# RS485.net
KiCad netlist of a schematic drawn in Altium Designer
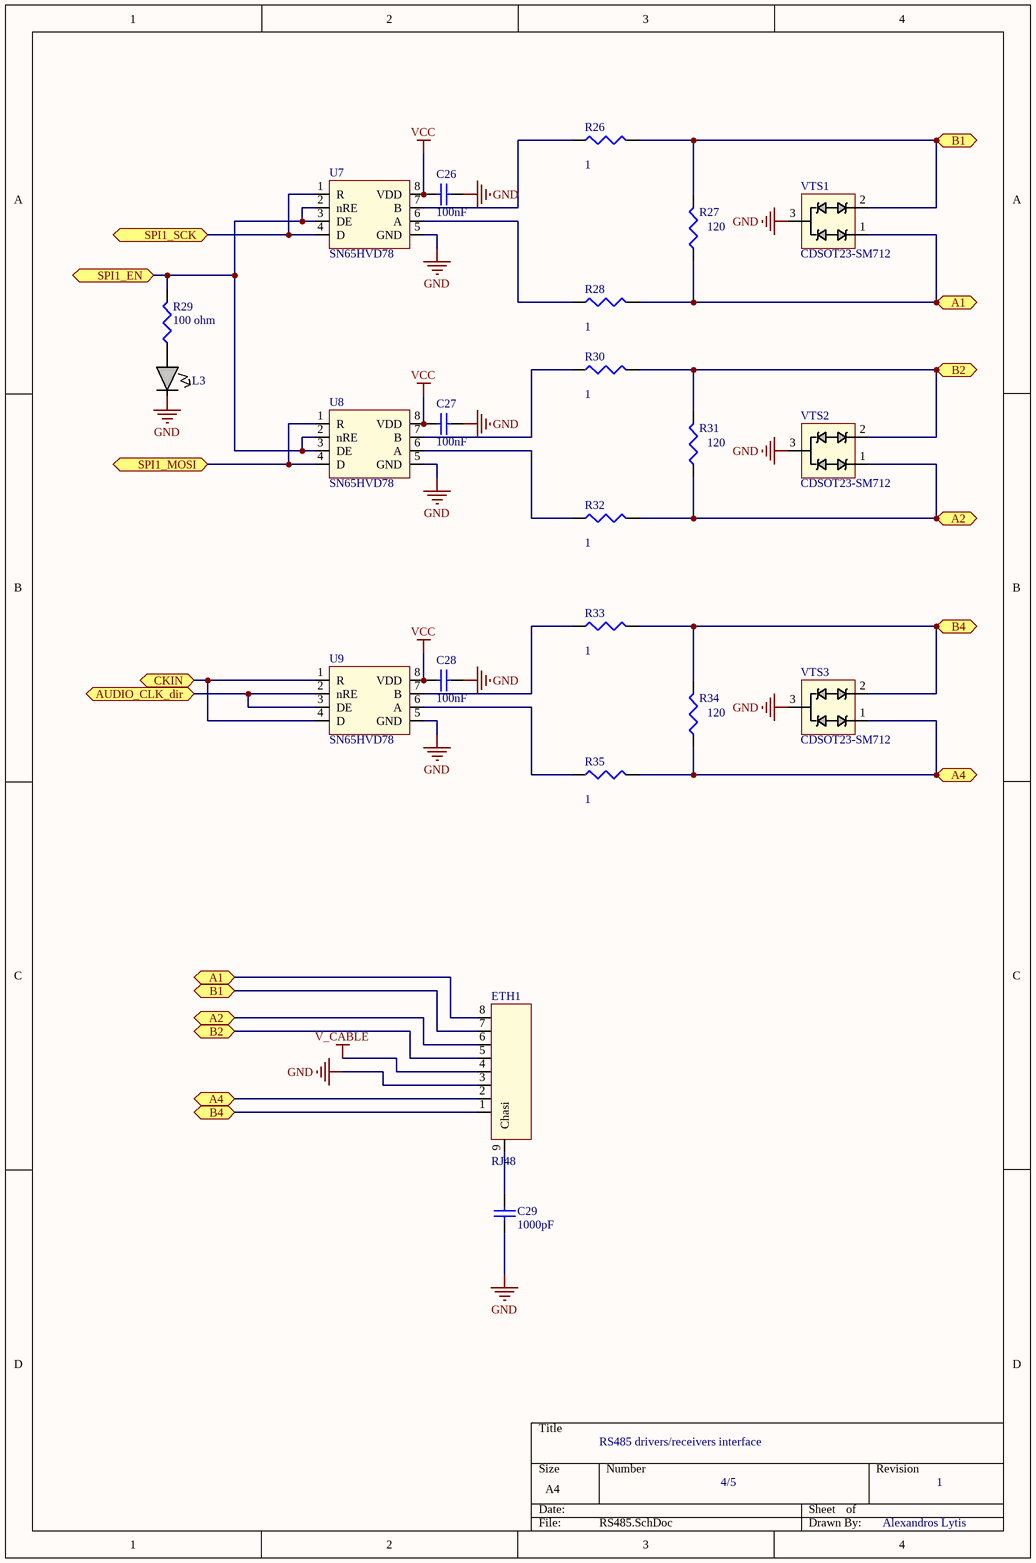
[diagram p0: RS485.SchDoc]

(export (version "E")
  (design (tool "Eeschema 10.0.6"))
  (components
    (comp (ref "C26")
      (value "100nF")
      (footprint "CAP0603")
      (description "Capacitor (Semiconductor SIM Model)")
      (fields (field (name "Comment") "Cap Semi") (field (name "PUBLISHER") "Altium Limited"))
      (libsource (lib "Miscellaneous Devices") (part "Cap Semi"))
    )
    (comp (ref "C27")
      (value "100nF")
      (footprint "CAP0603")
      (description "Capacitor (Semiconductor SIM Model)")
      (fields (field (name "Comment") "Cap Semi") (field (name "PUBLISHER") "Altium Limited"))
      (libsource (lib "Miscellaneous Devices") (part "Cap Semi"))
    )
    (comp (ref "C28")
      (value "100nF")
      (footprint "CAP0603")
      (description "Capacitor (Semiconductor SIM Model)")
      (fields (field (name "Comment") "Cap Semi") (field (name "PUBLISHER") "Altium Limited"))
      (libsource (lib "Miscellaneous Devices") (part "Cap Semi"))
    )
    (comp (ref "C29")
      (value "1000pF")
      (footprint "CAP0603")
      (description "Capacitor (Semiconductor SIM Model)")
      (fields (field (name "Comment") "Cap Semi") (field (name "PUBLISHER") "Altium Limited"))
      (libsource (lib "Miscellaneous Devices") (part "Cap Semi"))
    )
    (comp (ref "ETH1")
      (value "RJ48")
      (footprint "TE modular Jack RJ45")
      (libsource (lib "Custom_Libraries") (part "Ethernet Jack"))
    )
    (comp (ref "L3")
      (value "LED_1.6x0.8mm")
      (footprint "J1-0603")
      (libsource (lib "Custom_Libraries") (part "LED_1.6x0.8mm"))
    )
    (comp (ref "R26")
      (value "1")
      (footprint "RES0603")
      (description "Resistor")
      (fields (field (name "Comment") "pulse-proof") (field (name "PUBLISHER") "Altium Limited"))
      (libsource (lib "Miscellaneous Devices") (part "Res3"))
    )
    (comp (ref "R27")
      (value "120")
      (footprint "RES0603")
      (description "Resistor")
      (fields (field (name "Comment") "pulse-proof") (field (name "PUBLISHER") "Altium Limited"))
      (libsource (lib "Miscellaneous Devices") (part "Res3"))
    )
    (comp (ref "R28")
      (value "1")
      (footprint "RES0603")
      (description "Resistor")
      (fields (field (name "Comment") "pulse-proof") (field (name "PUBLISHER") "Altium Limited"))
      (libsource (lib "Miscellaneous Devices") (part "Res3"))
    )
    (comp (ref "R29")
      (value "100 ohm")
      (footprint "RES0603")
      (description "Resistor")
      (fields (field (name "Comment") "Res3") (field (name "PUBLISHER") "Altium Limited"))
      (libsource (lib "Miscellaneous Devices") (part "Res3"))
    )
    (comp (ref "R30")
      (value "1")
      (footprint "RES0603")
      (description "Resistor")
      (fields (field (name "Comment") "pulse-proof") (field (name "PUBLISHER") "Altium Limited"))
      (libsource (lib "Miscellaneous Devices") (part "Res3"))
    )
    (comp (ref "R31")
      (value "120")
      (footprint "RES0603")
      (description "Resistor")
      (fields (field (name "Comment") "pulse-proof") (field (name "PUBLISHER") "Altium Limited"))
      (libsource (lib "Miscellaneous Devices") (part "Res3"))
    )
    (comp (ref "R32")
      (value "1")
      (footprint "RES0603")
      (description "Resistor")
      (fields (field (name "Comment") "pulse-proof") (field (name "PUBLISHER") "Altium Limited"))
      (libsource (lib "Miscellaneous Devices") (part "Res3"))
    )
    (comp (ref "R33")
      (value "1")
      (footprint "RES0603")
      (description "Resistor")
      (fields (field (name "Comment") "pulse-proof") (field (name "PUBLISHER") "Altium Limited"))
      (libsource (lib "Miscellaneous Devices") (part "Res3"))
    )
    (comp (ref "R34")
      (value "120")
      (footprint "RES0603")
      (description "Resistor")
      (fields (field (name "Comment") "pulse-proof") (field (name "PUBLISHER") "Altium Limited"))
      (libsource (lib "Miscellaneous Devices") (part "Res3"))
    )
    (comp (ref "R35")
      (value "1")
      (footprint "RES0603")
      (description "Resistor")
      (fields (field (name "Comment") "pulse-proof") (field (name "PUBLISHER") "Altium Limited"))
      (libsource (lib "Miscellaneous Devices") (part "Res3"))
    )
    (comp (ref "U7")
      (value "SN65HVD78")
      (footprint "SOP127P600-8N")
      (libsource (lib "Custom_Libraries") (part "sn65hvd7x"))
    )
    (comp (ref "U8")
      (value "SN65HVD78")
      (footprint "SOP127P600-8N")
      (libsource (lib "Custom_Libraries") (part "sn65hvd7x"))
    )
    (comp (ref "U9")
      (value "SN65HVD78")
      (footprint "SOP127P600-8N")
      (libsource (lib "Custom_Libraries") (part "sn65hvd7x"))
    )
    (comp (ref "VTS1")
      (value "CDSOT23-SM712")
      (footprint "SOT190P230X117-3N")
      (libsource (lib "Custom_Libraries") (part "CDSOT23-SM712"))
    )
    (comp (ref "VTS2")
      (value "CDSOT23-SM712")
      (footprint "SOT190P230X117-3N")
      (libsource (lib "Custom_Libraries") (part "CDSOT23-SM712"))
    )
    (comp (ref "VTS3")
      (value "CDSOT23-SM712")
      (footprint "SOT190P230X117-3N")
      (libsource (lib "Custom_Libraries") (part "CDSOT23-SM712"))
    )
  )
  (nets
    (net (code "1") (name "/A1") (class "Default")
      (node (ref "ETH1") (pin "8") (pintype "passive"))
      (node (ref "R27") (pin "1") (pinfunction "1_1") (pintype "passive"))
      (node (ref "R28") (pin "2") (pinfunction "2_2") (pintype "passive"))
      (node (ref "VTS1") (pin "1") (pintype "passive"))
    )
    (net (code "2") (name "/A2") (class "Default")
      (node (ref "ETH1") (pin "6") (pintype "passive"))
      (node (ref "R31") (pin "1") (pinfunction "1_1") (pintype "passive"))
      (node (ref "R32") (pin "2") (pinfunction "2_2") (pintype "passive"))
      (node (ref "VTS2") (pin "1") (pintype "passive"))
    )
    (net (code "3") (name "/A4") (class "Default")
      (node (ref "ETH1") (pin "2") (pintype "passive"))
      (node (ref "R34") (pin "1") (pinfunction "1_1") (pintype "passive"))
      (node (ref "R35") (pin "2") (pinfunction "2_2") (pintype "passive"))
      (node (ref "VTS3") (pin "1") (pintype "passive"))
    )
    (net (code "4") (name "/AUDIO_CLK_dir") (class "Default")
      (node (ref "U9") (pin "2") (pinfunction "nRE_2") (pintype "passive"))
      (node (ref "U9") (pin "3") (pinfunction "DE_3") (pintype "passive"))
    )
    (net (code "5") (name "/B1") (class "Default")
      (node (ref "ETH1") (pin "7") (pintype "passive"))
      (node (ref "R26") (pin "2") (pinfunction "2_2") (pintype "passive"))
      (node (ref "R27") (pin "2") (pinfunction "2_2") (pintype "passive"))
      (node (ref "VTS1") (pin "2") (pintype "passive"))
    )
    (net (code "6") (name "/B2") (class "Default")
      (node (ref "ETH1") (pin "5") (pintype "passive"))
      (node (ref "R30") (pin "2") (pinfunction "2_2") (pintype "passive"))
      (node (ref "R31") (pin "2") (pinfunction "2_2") (pintype "passive"))
      (node (ref "VTS2") (pin "2") (pintype "passive"))
    )
    (net (code "7") (name "/B4") (class "Default")
      (node (ref "ETH1") (pin "1") (pintype "passive"))
      (node (ref "R33") (pin "2") (pinfunction "2_2") (pintype "passive"))
      (node (ref "R34") (pin "2") (pinfunction "2_2") (pintype "passive"))
      (node (ref "VTS3") (pin "2") (pintype "passive"))
    )
    (net (code "8") (name "/CKIN") (class "Default")
      (node (ref "U9") (pin "1") (pinfunction "R_1") (pintype "passive"))
      (node (ref "U9") (pin "4") (pinfunction "D_4") (pintype "passive"))
    )
    (net (code "9") (name "/SPI1_EN") (class "Default")
      (node (ref "R29") (pin "2") (pinfunction "2_2") (pintype "passive"))
      (node (ref "U7") (pin "2") (pinfunction "nRE_2") (pintype "passive"))
      (node (ref "U7") (pin "3") (pinfunction "DE_3") (pintype "passive"))
      (node (ref "U8") (pin "2") (pinfunction "nRE_2") (pintype "passive"))
      (node (ref "U8") (pin "3") (pinfunction "DE_3") (pintype "passive"))
    )
    (net (code "10") (name "/SPI1_MOSI") (class "Default")
      (node (ref "U8") (pin "1") (pinfunction "R_1") (pintype "passive"))
      (node (ref "U8") (pin "4") (pinfunction "D_4") (pintype "passive"))
    )
    (net (code "11") (name "/SPI1_SCK") (class "Default")
      (node (ref "U7") (pin "1") (pinfunction "R_1") (pintype "passive"))
      (node (ref "U7") (pin "4") (pinfunction "D_4") (pintype "passive"))
    )
    (net (code "12") (name "GND") (class "Default")
      (node (ref "C26") (pin "2") (pinfunction "2_2") (pintype "passive"))
      (node (ref "C27") (pin "2") (pinfunction "2_2") (pintype "passive"))
      (node (ref "C28") (pin "2") (pinfunction "2_2") (pintype "passive"))
      (node (ref "C29") (pin "1") (pinfunction "1_1") (pintype "passive"))
      (node (ref "ETH1") (pin "3") (pintype "passive"))
      (node (ref "L3") (pin "2") (pintype "passive"))
      (node (ref "U7") (pin "5") (pinfunction "GND_5") (pintype "passive"))
      (node (ref "U8") (pin "5") (pinfunction "GND_5") (pintype "passive"))
      (node (ref "U9") (pin "5") (pinfunction "GND_5") (pintype "passive"))
      (node (ref "VTS1") (pin "3") (pintype "passive"))
      (node (ref "VTS2") (pin "3") (pintype "passive"))
      (node (ref "VTS3") (pin "3") (pintype "passive"))
    )
    (net (code "13") (name "Net-(ETH1-Chasi)") (class "Default")
      (node (ref "C29") (pin "2") (pinfunction "2_2") (pintype "passive"))
      (node (ref "ETH1") (pin "9") (pinfunction "Chasi_9") (pintype "passive"))
    )
    (net (code "14") (name "Net-(L3-Pad1)") (class "Default")
      (node (ref "L3") (pin "1") (pintype "passive"))
      (node (ref "R29") (pin "1") (pinfunction "1_1") (pintype "passive"))
    )
    (net (code "15") (name "Net-(U7-A)") (class "Default")
      (node (ref "R28") (pin "1") (pinfunction "1_1") (pintype "passive"))
      (node (ref "U7") (pin "6") (pinfunction "A_6") (pintype "passive"))
    )
    (net (code "16") (name "Net-(U7-B)") (class "Default")
      (node (ref "R26") (pin "1") (pinfunction "1_1") (pintype "passive"))
      (node (ref "U7") (pin "7") (pinfunction "B_7") (pintype "passive"))
    )
    (net (code "17") (name "Net-(U8-A)") (class "Default")
      (node (ref "R32") (pin "1") (pinfunction "1_1") (pintype "passive"))
      (node (ref "U8") (pin "6") (pinfunction "A_6") (pintype "passive"))
    )
    (net (code "18") (name "Net-(U8-B)") (class "Default")
      (node (ref "R30") (pin "1") (pinfunction "1_1") (pintype "passive"))
      (node (ref "U8") (pin "7") (pinfunction "B_7") (pintype "passive"))
    )
    (net (code "19") (name "Net-(U9-A)") (class "Default")
      (node (ref "R35") (pin "1") (pinfunction "1_1") (pintype "passive"))
      (node (ref "U9") (pin "6") (pinfunction "A_6") (pintype "passive"))
    )
    (net (code "20") (name "Net-(U9-B)") (class "Default")
      (node (ref "R33") (pin "1") (pinfunction "1_1") (pintype "passive"))
      (node (ref "U9") (pin "7") (pinfunction "B_7") (pintype "passive"))
    )
    (net (code "21") (name "VCC") (class "Default")
      (node (ref "C26") (pin "1") (pinfunction "1_1") (pintype "passive"))
      (node (ref "C27") (pin "1") (pinfunction "1_1") (pintype "passive"))
      (node (ref "C28") (pin "1") (pinfunction "1_1") (pintype "passive"))
      (node (ref "U7") (pin "8") (pinfunction "VDD_8") (pintype "passive"))
      (node (ref "U8") (pin "8") (pinfunction "VDD_8") (pintype "passive"))
      (node (ref "U9") (pin "8") (pinfunction "VDD_8") (pintype "passive"))
    )
    (net (code "22") (name "V_CABLE") (class "Default") (node (ref "ETH1") (pin "4") (pintype "passive")))
  )
)
